# ESP32_MCU.net
KiCad netlist of a schematic drawn in Altium Designer
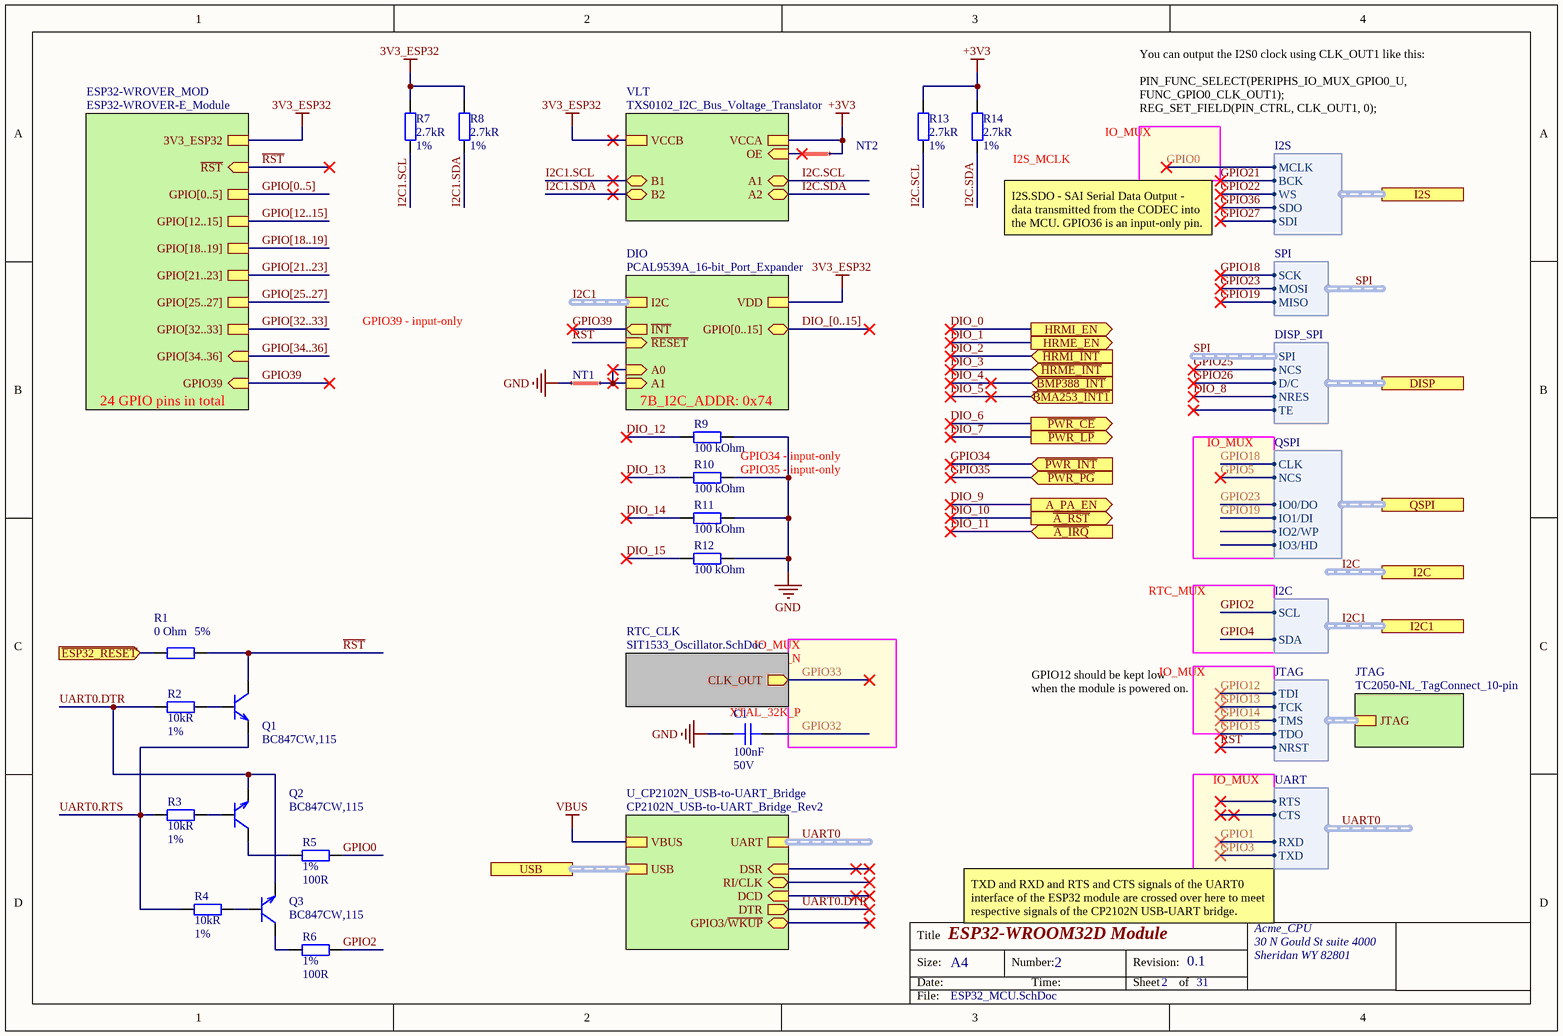
[diagram p0: ESP32_MCU.SchDoc]

(export (version "E")
  (design (tool "Eeschema 10.0.6"))
  (components
    (comp (ref "C1")
      (value "CAP CER 0.1UF 50V X7R 0402")
      (footprint "C0402")
      (description "0.1µF ±10% 50V Ceramic Capacitor X7R 0402 (1005 Metric)")
      (fields
        (field (name "MANUFACTURER") "TDK")
        (field (name "MANUFACTURER PART NUMBER") "CGA2B3X7R1H104K050BB")
        (field (name "CAPACITANCE") "100nF")
        (field (name "VOLTAGE") "50V")
      )
      (libsource (lib "capacitors_smd") (part "CAP CER 0.1UF 50V X7R 0402"))
    )
    (comp (ref "NT1")
      (value "Net Tie")
      (footprint "Net Tie 6x30mil")
      (libsource (lib "") (part "Net Tie Line_1"))
    )
    (comp (ref "NT2")
      (value "Net Tie")
      (footprint "Net Tie 6x30mil")
      (libsource (lib "BLDC_Motor_Driver") (part "Net Tie Line"))
    )
    (comp (ref "Q1")
      (value "BC847CW,115")
      (footprint "SOT-323")
      (description "Bipolar (BJT) Transistor NPN 45V 100mA 100MHz 200mW Surface Mount SOT-323-3")
      (fields (field (name "MANUFACTURER") "Nexperia"))
      (libsource (lib "bipolar-junction_transistors") (part "TRANS BC847CW,115 NPN 45V 0.1A SOT323"))
    )
    (comp (ref "Q2")
      (value "BC847CW,115")
      (footprint "SOT-323")
      (description "Bipolar (BJT) Transistor NPN 45V 100mA 100MHz 200mW Surface Mount SOT-323-3")
      (fields (field (name "MANUFACTURER") "Nexperia"))
      (libsource (lib "bipolar-junction_transistors") (part "TRANS BC847CW,115 NPN 45V 0.1A SOT323"))
    )
    (comp (ref "Q3")
      (value "BC847CW,115")
      (footprint "SOT-323")
      (description "Bipolar (BJT) Transistor NPN 45V 100mA 100MHz 200mW Surface Mount SOT-323-3")
      (fields (field (name "MANUFACTURER") "Nexperia"))
      (libsource (lib "bipolar-junction_transistors") (part "TRANS BC847CW,115 NPN 45V 0.1A SOT323"))
    )
    (comp (ref "R1")
      (value "RES SMD 0 OHM JUMPER 1/16W 0402")
      (footprint "R0402")
      (description "0 Ohms Jumper 0.063W, 1/16W Chip Resistor 0402 (1005 Metric) Moisture Resistant Thick Film")
      (fields
        (field (name "MANUFACTURER") "Yageo")
        (field (name "MANUFACTURER PART NUMBER") "RC0402JR-070RL")
        (field (name "TOLERANCE") "5%")
        (field (name "RESISTANCE") "0 Ohm")
      )
      (libsource (lib "resistors_smd") (part "RES SMD 0 OHM JUMPER 1/16W 0402"))
    )
    (comp (ref "R2")
      (value "RES SMD 10K OHM 1% 1/16W 0402")
      (footprint "R0402")
      (description "10 kOhms ±1% 0.063W, 1/16W Chip Resistor 0402 (1005 Metric) Moisture Resistant Thick Film")
      (fields
        (field (name "MANUFACTURER PART NUMBER") "RC0402FR-0710KP")
        (field (name "MANUFACTURER") "Yageo")
        (field (name "RESISTANCE") "10kR")
        (field (name "TOLERANCE") "1%")
      )
      (libsource (lib "resistors_smd") (part "RES SMD 10K OHM 1% 1/16W 0402"))
    )
    (comp (ref "R3")
      (value "RES SMD 10K OHM 1% 1/16W 0402")
      (footprint "R0402")
      (description "10 kOhms ±1% 0.063W, 1/16W Chip Resistor 0402 (1005 Metric) Moisture Resistant Thick Film")
      (fields
        (field (name "MANUFACTURER PART NUMBER") "RC0402FR-0710KP")
        (field (name "MANUFACTURER") "Yageo")
        (field (name "RESISTANCE") "10kR")
        (field (name "TOLERANCE") "1%")
      )
      (libsource (lib "resistors_smd") (part "RES SMD 10K OHM 1% 1/16W 0402"))
    )
    (comp (ref "R4")
      (value "RES SMD 10K OHM 1% 1/16W 0402")
      (footprint "R0402")
      (description "10 kOhms ±1% 0.063W, 1/16W Chip Resistor 0402 (1005 Metric) Moisture Resistant Thick Film")
      (fields
        (field (name "MANUFACTURER PART NUMBER") "RC0402FR-0710KP")
        (field (name "MANUFACTURER") "Yageo")
        (field (name "RESISTANCE") "10kR")
        (field (name "TOLERANCE") "1%")
      )
      (libsource (lib "resistors_smd") (part "RES SMD 10K OHM 1% 1/16W 0402"))
    )
    (comp (ref "R5")
      (value "RES SMD 100 OHM 1% 1/16W 0402")
      (footprint "0402R")
      (description "100 Ohms ±1% 0.063W, 1/16W Chip Resistor 0402 (1005 Metric) Moisture Resistant Thick Film")
      (fields
        (field (name "MANUFACTURER") "Yageo")
        (field (name "MANUFACTURER PART NUMBER") "RC0402FR-07100RL")
        (field (name "TOLERANCE") "1%")
        (field (name "RESISTANCE") "100R")
      )
      (libsource (lib "resistors_smd") (part "RES SMD 100 OHM 1% 1/16W 0402"))
    )
    (comp (ref "R6")
      (value "RES SMD 100 OHM 1% 1/16W 0402")
      (footprint "0402R")
      (description "100 Ohms ±1% 0.063W, 1/16W Chip Resistor 0402 (1005 Metric) Moisture Resistant Thick Film")
      (fields
        (field (name "MANUFACTURER") "Yageo")
        (field (name "MANUFACTURER PART NUMBER") "RC0402FR-07100RL")
        (field (name "TOLERANCE") "1%")
        (field (name "RESISTANCE") "100R")
      )
      (libsource (lib "resistors_smd") (part "RES SMD 100 OHM 1% 1/16W 0402"))
    )
    (comp (ref "R7")
      (value "RES SMD 2.7K OHM 1% 1/16W 0402")
      (footprint "R0402")
      (description "2.7 kOhms ±1% 0.063W, 1/16W Chip Resistor 0402 (1005 Metric) Moisture Resistant Thick Film")
      (fields
        (field (name "MANUFACTURER PART NUMBER") "RC0402FR-072K7L")
        (field (name "MANUFACTURER") "Yageo")
        (field (name "RESISTANCE") "2.7kR")
        (field (name "TOLERANCE") "1%")
      )
      (libsource (lib "resistors_smd") (part "RES SMD 2.7K OHM 1% 1/16W 0402"))
    )
    (comp (ref "R8")
      (value "RES SMD 2.7K OHM 1% 1/16W 0402")
      (footprint "R0402")
      (description "2.7 kOhms ±1% 0.063W, 1/16W Chip Resistor 0402 (1005 Metric) Moisture Resistant Thick Film")
      (fields
        (field (name "MANUFACTURER PART NUMBER") "RC0402FR-072K7L")
        (field (name "MANUFACTURER") "Yageo")
        (field (name "RESISTANCE") "2.7kR")
        (field (name "TOLERANCE") "1%")
      )
      (libsource (lib "resistors_smd") (part "RES SMD 2.7K OHM 1% 1/16W 0402"))
    )
    (comp (ref "R9")
      (value "RES SMD 100K OHM 1% 1/16W 0402")
      (footprint "0402R")
      (description "100 kOhms ±1% 0.063W, 1/16W Chip Resistor 0402 (1005 Metric) Moisture Resistant Thick Film")
      (fields
        (field (name "MANUFACTURER") "Yageo")
        (field (name "MANUFACTURER PART NUMBER") "RC0402FR-07100KL")
        (field (name "RESISTANCE") "100 kOhm")
      )
      (libsource (lib "resistors_smd") (part "RES SMD 100K OHM 1% 1/16W 0402"))
    )
    (comp (ref "R10")
      (value "RES SMD 100K OHM 1% 1/16W 0402")
      (footprint "0402R")
      (description "100 kOhms ±1% 0.063W, 1/16W Chip Resistor 0402 (1005 Metric) Moisture Resistant Thick Film")
      (fields
        (field (name "MANUFACTURER") "Yageo")
        (field (name "MANUFACTURER PART NUMBER") "RC0402FR-07100KL")
        (field (name "RESISTANCE") "100 kOhm")
      )
      (libsource (lib "resistors_smd") (part "RES SMD 100K OHM 1% 1/16W 0402"))
    )
    (comp (ref "R11")
      (value "RES SMD 100K OHM 1% 1/16W 0402")
      (footprint "0402R")
      (description "100 kOhms ±1% 0.063W, 1/16W Chip Resistor 0402 (1005 Metric) Moisture Resistant Thick Film")
      (fields
        (field (name "MANUFACTURER") "Yageo")
        (field (name "MANUFACTURER PART NUMBER") "RC0402FR-07100KL")
        (field (name "RESISTANCE") "100 kOhm")
      )
      (libsource (lib "resistors_smd") (part "RES SMD 100K OHM 1% 1/16W 0402"))
    )
    (comp (ref "R12")
      (value "RES SMD 100K OHM 1% 1/16W 0402")
      (footprint "0402R")
      (description "100 kOhms ±1% 0.063W, 1/16W Chip Resistor 0402 (1005 Metric) Moisture Resistant Thick Film")
      (fields
        (field (name "MANUFACTURER") "Yageo")
        (field (name "MANUFACTURER PART NUMBER") "RC0402FR-07100KL")
        (field (name "RESISTANCE") "100 kOhm")
      )
      (libsource (lib "resistors_smd") (part "RES SMD 100K OHM 1% 1/16W 0402"))
    )
    (comp (ref "R13")
      (value "RES SMD 2.7K OHM 1% 1/16W 0402")
      (footprint "R0402")
      (description "2.7 kOhms ±1% 0.063W, 1/16W Chip Resistor 0402 (1005 Metric) Moisture Resistant Thick Film")
      (fields
        (field (name "MANUFACTURER PART NUMBER") "RC0402FR-072K7L")
        (field (name "MANUFACTURER") "Yageo")
        (field (name "RESISTANCE") "2.7kR")
        (field (name "TOLERANCE") "1%")
      )
      (libsource (lib "resistors_smd") (part "RES SMD 2.7K OHM 1% 1/16W 0402"))
    )
    (comp (ref "R14")
      (value "RES SMD 2.7K OHM 1% 1/16W 0402")
      (footprint "R0402")
      (description "2.7 kOhms ±1% 0.063W, 1/16W Chip Resistor 0402 (1005 Metric) Moisture Resistant Thick Film")
      (fields
        (field (name "MANUFACTURER PART NUMBER") "RC0402FR-072K7L")
        (field (name "MANUFACTURER") "Yageo")
        (field (name "RESISTANCE") "2.7kR")
        (field (name "TOLERANCE") "1%")
      )
      (libsource (lib "resistors_smd") (part "RES SMD 2.7K OHM 1% 1/16W 0402"))
    )
  )
  (nets
    (net (code "13") (name "+3V3") (class "Default")
      (node (ref "NT2") (pin "2") (pintype "passive"))
      (node (ref "R13") (pin "2") (pinfunction "2_2") (pintype "passive"))
      (node (ref "R14") (pin "2") (pinfunction "2_2") (pintype "passive"))
    )
    (net (code "14") (name "/A0") (class "Default")
      (node (ref "NT1") (pin "2") (pintype "passive+no_connect"))
    )
    (net (code "28") (name "/DIO_12") (class "Default")
      (node (ref "R9") (pin "1") (pinfunction "1_1") (pintype "passive+no_connect"))
    )
    (net (code "29") (name "/DIO_13") (class "Default")
      (node (ref "R10") (pin "1") (pinfunction "1_1") (pintype "passive+no_connect"))
    )
    (net (code "30") (name "/DIO_14") (class "Default")
      (node (ref "R11") (pin "1") (pinfunction "1_1") (pintype "passive+no_connect"))
    )
    (net (code "31") (name "/DIO_15") (class "Default")
      (node (ref "R12") (pin "1") (pinfunction "1_1") (pintype "passive+no_connect"))
    )
    (net (code "34") (name "/ESP32_RESET") (class "Default")
      (node (ref "R1") (pin "1") (pinfunction "1_1") (pintype "passive"))
    )
    (net (code "35") (name "/GPIO0") (class "Default")
      (node (ref "R5") (pin "1") (pinfunction "1_1") (pintype "passive+no_connect"))
    )
    (net (code "37") (name "/GPIO2") (class "Default")
      (node (ref "R6") (pin "1") (pinfunction "1_1") (pintype "passive"))
    )
    (net (code "54") (name "/GPIO32") (class "Default")
      (node (ref "C1") (pin "1") (pinfunction "1_1") (pintype "passive"))
    )
    (net (code "67") (name "/I2C.SCL") (class "Default")
      (node (ref "R13") (pin "1") (pinfunction "1_1") (pintype "passive"))
    )
    (net (code "68") (name "/I2C.SDA") (class "Default")
      (node (ref "R14") (pin "1") (pinfunction "1_1") (pintype "passive"))
    )
    (net (code "69") (name "/I2C1.SCL") (class "Default")
      (node (ref "R7") (pin "1") (pinfunction "1_1") (pintype "passive"))
    )
    (net (code "70") (name "/I2C1.SDA") (class "Default")
      (node (ref "R8") (pin "1") (pinfunction "1_1") (pintype "passive"))
    )
    (net (code "72") (name "/OE") (class "Default")
      (node (ref "NT2") (pin "1") (pintype "passive+no_connect"))
    )
    (net (code "74") (name "/RST") (class "Default")
      (node (ref "Q1") (pin "3") (pinfunction "C_3") (pintype "passive"))
      (node (ref "R1") (pin "2") (pinfunction "2_2") (pintype "passive"))
    )
    (net (code "76") (name "/UART0.DTR") (class "Default")
      (node (ref "Q2") (pin "2") (pinfunction "E_2") (pintype "passive"))
      (node (ref "Q3") (pin "2") (pinfunction "E_2") (pintype "passive"))
      (node (ref "R2") (pin "1") (pinfunction "1_1") (pintype "passive"))
    )
    (net (code "77") (name "/UART0.RTS") (class "Default")
      (node (ref "Q1") (pin "2") (pinfunction "E_2") (pintype "passive"))
      (node (ref "R3") (pin "1") (pinfunction "1_1") (pintype "passive"))
      (node (ref "R4") (pin "1") (pinfunction "1_1") (pintype "passive"))
    )
    (net (code "88") (name "3V3_ESP32") (class "Default")
      (node (ref "R7") (pin "2") (pinfunction "2_2") (pintype "passive"))
      (node (ref "R8") (pin "2") (pinfunction "2_2") (pintype "passive"))
    )
    (net (code "89") (name "GND") (class "Default")
      (node (ref "C1") (pin "2") (pinfunction "2_2") (pintype "passive"))
      (node (ref "NT1") (pin "1") (pintype "passive"))
      (node (ref "R10") (pin "2") (pinfunction "2_2") (pintype "passive"))
      (node (ref "R11") (pin "2") (pinfunction "2_2") (pintype "passive"))
      (node (ref "R12") (pin "2") (pinfunction "2_2") (pintype "passive"))
      (node (ref "R9") (pin "2") (pinfunction "2_2") (pintype "passive"))
    )
    (net (code "90") (name "Net-(Q1-B)") (class "Default")
      (node (ref "Q1") (pin "1") (pinfunction "B_1") (pintype "passive"))
      (node (ref "R2") (pin "2") (pinfunction "2_2") (pintype "passive"))
    )
    (net (code "91") (name "Net-(Q2-B)") (class "Default")
      (node (ref "Q2") (pin "1") (pinfunction "B_1") (pintype "passive"))
      (node (ref "R3") (pin "2") (pinfunction "2_2") (pintype "passive"))
    )
    (net (code "92") (name "Net-(Q2-C)") (class "Default")
      (node (ref "Q2") (pin "3") (pinfunction "C_3") (pintype "passive"))
      (node (ref "R5") (pin "2") (pinfunction "2_2") (pintype "passive"))
    )
    (net (code "93") (name "Net-(Q3-B)") (class "Default")
      (node (ref "Q3") (pin "1") (pinfunction "B_1") (pintype "passive"))
      (node (ref "R4") (pin "2") (pinfunction "2_2") (pintype "passive"))
    )
    (net (code "94") (name "Net-(Q3-C)") (class "Default")
      (node (ref "Q3") (pin "3") (pinfunction "C_3") (pintype "passive"))
      (node (ref "R6") (pin "2") (pinfunction "2_2") (pintype "passive"))
    )
  )
)
